# Relay_Sequencer.net
KiCad netlist of a schematic drawn in EAGLE
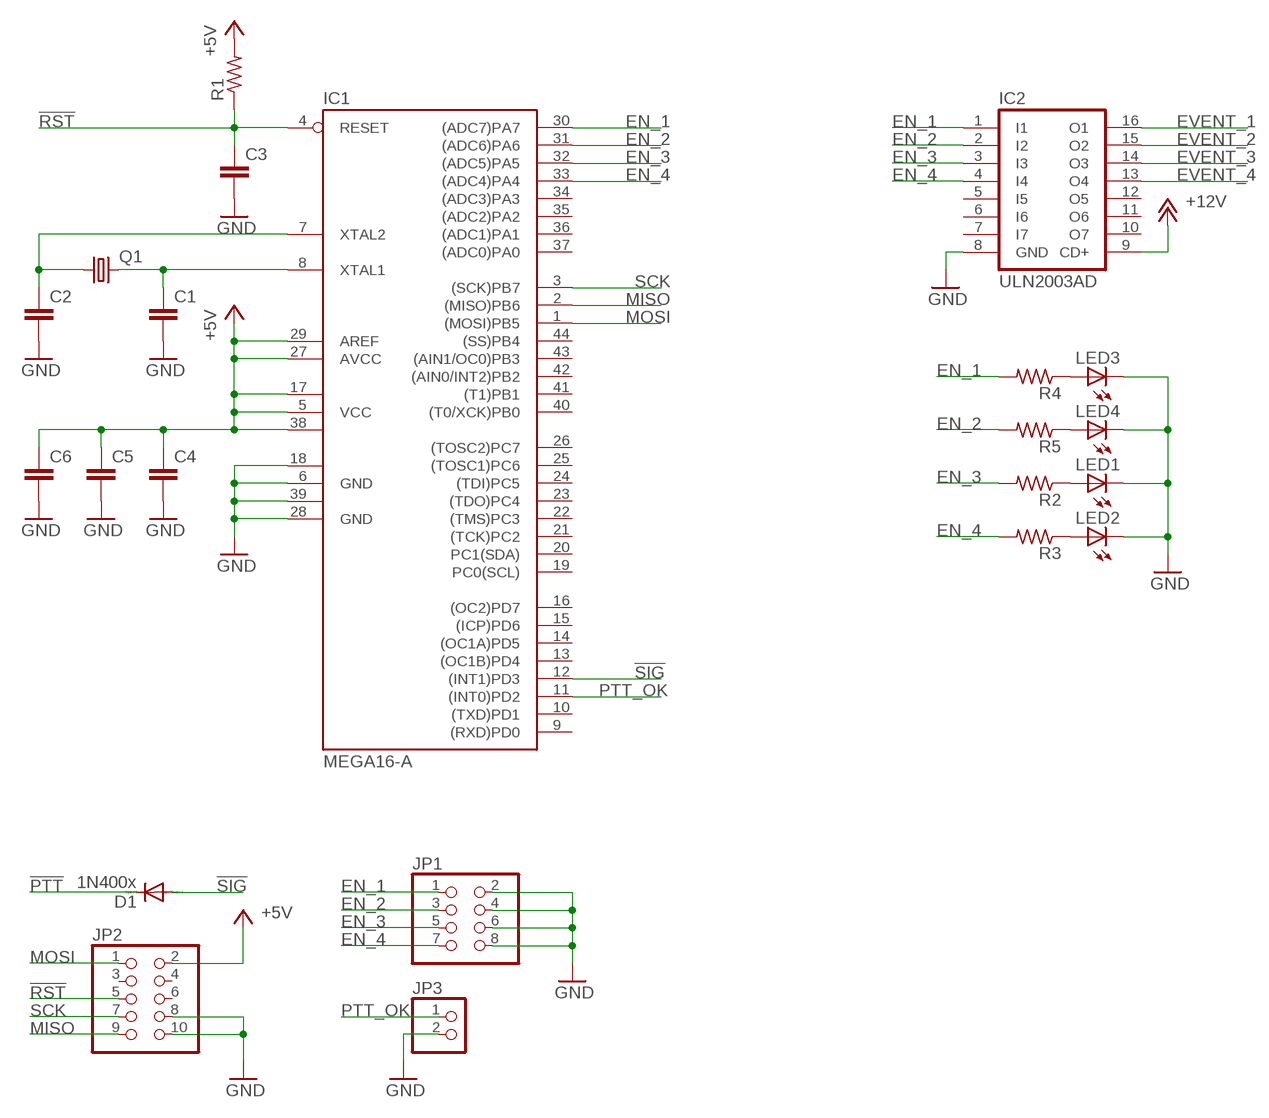
[diagram p0: schematic, sheet 1]

(export (version "E")
  (design (tool "Eeschema 10.0.6"))
  (components
    (comp (ref "C1")
      (value "C-EUC1206")
      (footprint "eagle-import:C1206")
      (libsource (lib "eagle-import") (part "C-EUC1206"))
    )
    (comp (ref "C2")
      (value "C-EUC1206")
      (footprint "eagle-import:C1206")
      (libsource (lib "eagle-import") (part "C-EUC1206"))
    )
    (comp (ref "C3")
      (value "C-EUC1206")
      (footprint "eagle-import:C1206")
      (libsource (lib "eagle-import") (part "C-EUC1206"))
    )
    (comp (ref "C4")
      (value "C-EUC1206")
      (footprint "eagle-import:C1206")
      (libsource (lib "eagle-import") (part "C-EUC1206"))
    )
    (comp (ref "C5")
      (value "C-EUC1206")
      (footprint "eagle-import:C1206")
      (libsource (lib "eagle-import") (part "C-EUC1206"))
    )
    (comp (ref "C6")
      (value "C-EUC1206")
      (footprint "eagle-import:C1206")
      (libsource (lib "eagle-import") (part "C-EUC1206"))
    )
    (comp (ref "D1")
      (value "1N400x")
      (footprint "eagle-import:DO35-10")
      (libsource (lib "eagle-import") (part "1N4148DO35-10"))
    )
    (comp (ref "IC1")
      (value "MEGA16-A")
      (footprint "eagle-import:TQFP44")
      (fields (field (name "MPN") "ATMEGA16-16AU"))
      (libsource (lib "eagle-import") (part "MEGA16-A"))
    )
    (comp (ref "IC2")
      (value "ULN2003AD")
      (footprint "eagle-import:SO16")
      (libsource (lib "eagle-import") (part "ULN2003AD"))
    )
    (comp (ref "JP1")
      (value "PINHD-2X4")
      (footprint "eagle-import:2X04")
      (libsource (lib "eagle-import") (part "PINHD-2X4"))
    )
    (comp (ref "JP2")
      (value "PINHD-2X5")
      (footprint "eagle-import:2X05")
      (libsource (lib "eagle-import") (part "PINHD-2X5"))
    )
    (comp (ref "JP3")
      (value "PINHD-1X2")
      (footprint "eagle-import:1X02")
      (libsource (lib "eagle-import") (part "PINHD-1X2"))
    )
    (comp (ref "LED1")
      (value "LED3MM")
      (footprint "eagle-import:LED3MM")
      (libsource (lib "eagle-import") (part "LED3MM"))
    )
    (comp (ref "LED2")
      (value "LED3MM")
      (footprint "eagle-import:LED3MM")
      (libsource (lib "eagle-import") (part "LED3MM"))
    )
    (comp (ref "LED3")
      (value "LED3MM")
      (footprint "eagle-import:LED3MM")
      (libsource (lib "eagle-import") (part "LED3MM"))
    )
    (comp (ref "LED4")
      (value "LED3MM")
      (footprint "eagle-import:LED3MM")
      (libsource (lib "eagle-import") (part "LED3MM"))
    )
    (comp (ref "Q1")
      (value "CRYSTALHC49S")
      (footprint "eagle-import:HC49_S")
      (libsource (lib "eagle-import") (part "CRYSTALHC49S"))
    )
    (comp (ref "R1")
      (value "R-US_M1206")
      (footprint "eagle-import:M1206")
      (libsource (lib "eagle-import") (part "R-US_M1206"))
    )
    (comp (ref "R2")
      (value "R-US_M1206")
      (footprint "eagle-import:M1206")
      (libsource (lib "eagle-import") (part "R-US_M1206"))
    )
    (comp (ref "R3")
      (value "R-US_M1206")
      (footprint "eagle-import:M1206")
      (libsource (lib "eagle-import") (part "R-US_M1206"))
    )
    (comp (ref "R4")
      (value "R-US_M1206")
      (footprint "eagle-import:M1206")
      (libsource (lib "eagle-import") (part "R-US_M1206"))
    )
    (comp (ref "R5")
      (value "R-US_M1206")
      (footprint "eagle-import:M1206")
      (libsource (lib "eagle-import") (part "R-US_M1206"))
    )
  )
  (nets
    (net (code "1") (name "+5V") (class "Default")
      (node (ref "C4") (pin "1") (pinfunction "1_1") (pintype "passive"))
      (node (ref "C5") (pin "1") (pinfunction "1_1") (pintype "passive"))
      (node (ref "C6") (pin "1") (pinfunction "1_1") (pintype "passive"))
      (node (ref "IC1") (pin "17") (pinfunction "VCC1_17") (pintype "power_in"))
      (node (ref "IC1") (pin "27") (pinfunction "AVCC_27") (pintype "power_in"))
      (node (ref "IC1") (pin "29") (pinfunction "AREF_29") (pintype "passive"))
      (node (ref "IC1") (pin "38") (pinfunction "VCC2_38") (pintype "power_in"))
      (node (ref "IC1") (pin "5") (pinfunction "VCC_5") (pintype "power_in"))
      (node (ref "JP2") (pin "2") (pinfunction "2_2") (pintype "passive"))
      (node (ref "R1") (pin "2") (pinfunction "2_2") (pintype "passive"))
    )
    (net (code "2") (name "+12V") (class "Default")
      (node (ref "IC2") (pin "9") (pinfunction "CD+_9") (pintype "passive"))
    )
    (net (code "3") (name "/EN_1") (class "Default")
      (node (ref "IC1") (pin "30") (pinfunction "(ADC7)PA7_30") (pintype "bidirectional"))
      (node (ref "IC2") (pin "1") (pinfunction "I1_1") (pintype "input"))
      (node (ref "JP1") (pin "1") (pinfunction "1_1") (pintype "passive"))
      (node (ref "R4") (pin "2") (pinfunction "2_2") (pintype "passive"))
    )
    (net (code "4") (name "/EN_2") (class "Default")
      (node (ref "IC1") (pin "31") (pinfunction "(ADC6)PA6_31") (pintype "bidirectional"))
      (node (ref "IC2") (pin "2") (pinfunction "I2_2") (pintype "input"))
      (node (ref "JP1") (pin "3") (pinfunction "3_3") (pintype "passive"))
      (node (ref "R5") (pin "2") (pinfunction "2_2") (pintype "passive"))
    )
    (net (code "5") (name "/EN_3") (class "Default")
      (node (ref "IC1") (pin "32") (pinfunction "(ADC5)PA5_32") (pintype "bidirectional"))
      (node (ref "IC2") (pin "3") (pinfunction "I3_3") (pintype "input"))
      (node (ref "JP1") (pin "5") (pinfunction "5_5") (pintype "passive"))
      (node (ref "R2") (pin "2") (pinfunction "2_2") (pintype "passive"))
    )
    (net (code "6") (name "/EN_4") (class "Default")
      (node (ref "IC1") (pin "33") (pinfunction "(ADC4)PA4_33") (pintype "bidirectional"))
      (node (ref "IC2") (pin "4") (pinfunction "I4_4") (pintype "input"))
      (node (ref "JP1") (pin "7") (pinfunction "7_7") (pintype "passive"))
      (node (ref "R3") (pin "2") (pinfunction "2_2") (pintype "passive"))
    )
    (net (code "7") (name "/EVENT_1") (class "Default")
      (node (ref "IC2") (pin "16") (pinfunction "O1_16") (pintype "open_collector"))
    )
    (net (code "8") (name "/EVENT_2") (class "Default")
      (node (ref "IC2") (pin "15") (pinfunction "O2_15") (pintype "open_collector"))
    )
    (net (code "9") (name "/EVENT_3") (class "Default")
      (node (ref "IC2") (pin "14") (pinfunction "O3_14") (pintype "open_collector"))
    )
    (net (code "10") (name "/EVENT_4") (class "Default")
      (node (ref "IC2") (pin "13") (pinfunction "O4_13") (pintype "open_collector"))
    )
    (net (code "11") (name "/MISO") (class "Default")
      (node (ref "IC1") (pin "2") (pinfunction "(MISO)PB6_2") (pintype "bidirectional"))
      (node (ref "JP2") (pin "9") (pinfunction "9_9") (pintype "passive"))
    )
    (net (code "12") (name "/MOSI") (class "Default")
      (node (ref "IC1") (pin "1") (pinfunction "(MOSI)PB5_1") (pintype "bidirectional"))
      (node (ref "JP2") (pin "1") (pinfunction "1_1") (pintype "passive"))
    )
    (net (code "13") (name "/PTT_OK") (class "Default")
      (node (ref "IC1") (pin "11") (pinfunction "(INT0)PD2_11") (pintype "bidirectional"))
      (node (ref "JP3") (pin "1") (pinfunction "1_1") (pintype "passive"))
    )
    (net (code "14") (name "/SCK") (class "Default")
      (node (ref "IC1") (pin "3") (pinfunction "(SCK)PB7_3") (pintype "bidirectional"))
      (node (ref "JP2") (pin "7") (pinfunction "7_7") (pintype "passive"))
    )
    (net (code "15") (name "/~{PTT}") (class "Default")
      (node (ref "D1") (pin "C") (pinfunction "C_C") (pintype "passive"))
    )
    (net (code "16") (name "/~{RST}") (class "Default")
      (node (ref "C3") (pin "1") (pinfunction "1_1") (pintype "passive"))
      (node (ref "IC1") (pin "4") (pinfunction "RESET_4") (pintype "input"))
      (node (ref "JP2") (pin "5") (pinfunction "5_5") (pintype "passive"))
      (node (ref "R1") (pin "1") (pinfunction "1_1") (pintype "passive"))
    )
    (net (code "17") (name "/~{SIG}") (class "Default")
      (node (ref "D1") (pin "A") (pinfunction "A_A") (pintype "passive"))
      (node (ref "IC1") (pin "12") (pinfunction "(INT1)PD3_12") (pintype "bidirectional"))
    )
    (net (code "18") (name "GND") (class "Default")
      (node (ref "C1") (pin "2") (pinfunction "2_2") (pintype "passive"))
      (node (ref "C2") (pin "2") (pinfunction "2_2") (pintype "passive"))
      (node (ref "C3") (pin "2") (pinfunction "2_2") (pintype "passive"))
      (node (ref "C4") (pin "2") (pinfunction "2_2") (pintype "passive"))
      (node (ref "C5") (pin "2") (pinfunction "2_2") (pintype "passive"))
      (node (ref "C6") (pin "2") (pinfunction "2_2") (pintype "passive"))
      (node (ref "IC1") (pin "18") (pinfunction "GND1_18") (pintype "power_in"))
      (node (ref "IC1") (pin "28") (pinfunction "GND_28") (pintype "power_in"))
      (node (ref "IC1") (pin "39") (pinfunction "GND2_39") (pintype "power_in"))
      (node (ref "IC1") (pin "6") (pinfunction "GND_6") (pintype "power_in"))
      (node (ref "IC2") (pin "8") (pinfunction "GND_8") (pintype "power_in"))
      (node (ref "JP1") (pin "2") (pinfunction "2_2") (pintype "passive"))
      (node (ref "JP1") (pin "4") (pinfunction "4_4") (pintype "passive"))
      (node (ref "JP1") (pin "6") (pinfunction "6_6") (pintype "passive"))
      (node (ref "JP1") (pin "8") (pinfunction "8_8") (pintype "passive"))
      (node (ref "JP2") (pin "10") (pinfunction "10_10") (pintype "passive"))
      (node (ref "JP2") (pin "8") (pinfunction "8_8") (pintype "passive"))
      (node (ref "JP3") (pin "2") (pinfunction "2_2") (pintype "passive"))
      (node (ref "LED1") (pin "K") (pinfunction "C_K") (pintype "passive"))
      (node (ref "LED2") (pin "K") (pinfunction "C_K") (pintype "passive"))
      (node (ref "LED3") (pin "K") (pinfunction "C_K") (pintype "passive"))
      (node (ref "LED4") (pin "K") (pinfunction "C_K") (pintype "passive"))
    )
    (net (code "19") (name "Net-(IC1-XTAL1)") (class "Default")
      (node (ref "C1") (pin "1") (pinfunction "1_1") (pintype "passive"))
      (node (ref "IC1") (pin "8") (pinfunction "XTAL1_8") (pintype "bidirectional"))
      (node (ref "Q1") (pin "2") (pinfunction "2_2") (pintype "passive"))
    )
    (net (code "20") (name "Net-(IC1-XTAL2)") (class "Default")
      (node (ref "C2") (pin "1") (pinfunction "1_1") (pintype "passive"))
      (node (ref "IC1") (pin "7") (pinfunction "XTAL2_7") (pintype "bidirectional"))
      (node (ref "Q1") (pin "1") (pinfunction "1_1") (pintype "passive"))
    )
    (net (code "21") (name "Net-(LED1-PadA)") (class "Default")
      (node (ref "LED1") (pin "A") (pinfunction "A_A") (pintype "passive"))
      (node (ref "R2") (pin "1") (pinfunction "1_1") (pintype "passive"))
    )
    (net (code "22") (name "Net-(LED2-PadA)") (class "Default")
      (node (ref "LED2") (pin "A") (pinfunction "A_A") (pintype "passive"))
      (node (ref "R3") (pin "1") (pinfunction "1_1") (pintype "passive"))
    )
    (net (code "23") (name "Net-(LED3-PadA)") (class "Default")
      (node (ref "LED3") (pin "A") (pinfunction "A_A") (pintype "passive"))
      (node (ref "R4") (pin "1") (pinfunction "1_1") (pintype "passive"))
    )
    (net (code "24") (name "Net-(LED4-PadA)") (class "Default")
      (node (ref "LED4") (pin "A") (pinfunction "A_A") (pintype "passive"))
      (node (ref "R5") (pin "1") (pinfunction "1_1") (pintype "passive"))
    )
    (net (code "25") (name "unconnected-(IC1-(ADC0)PA0-Pad37)") (class "Default")
      (node (ref "IC1") (pin "37") (pinfunction "(ADC0)PA0_37") (pintype "bidirectional"))
    )
    (net (code "26") (name "unconnected-(IC1-(ADC1)PA1-Pad36)") (class "Default")
      (node (ref "IC1") (pin "36") (pinfunction "(ADC1)PA1_36") (pintype "bidirectional"))
    )
    (net (code "27") (name "unconnected-(IC1-(ADC2)PA2-Pad35)") (class "Default")
      (node (ref "IC1") (pin "35") (pinfunction "(ADC2)PA2_35") (pintype "bidirectional"))
    )
    (net (code "28") (name "unconnected-(IC1-(ADC3)PA3-Pad34)") (class "Default")
      (node (ref "IC1") (pin "34") (pinfunction "(ADC3)PA3_34") (pintype "bidirectional"))
    )
    (net (code "29") (name "unconnected-(IC1-(AIN0{slash}INT2)PB2-Pad42)") (class "Default")
      (node (ref "IC1") (pin "42") (pinfunction "(AIN0/INT2)PB2_42") (pintype "bidirectional"))
    )
    (net (code "30") (name "unconnected-(IC1-(AIN1{slash}OC0)PB3-Pad43)") (class "Default")
      (node (ref "IC1") (pin "43") (pinfunction "(AIN1/OC0)PB3_43") (pintype "bidirectional"))
    )
    (net (code "31") (name "unconnected-(IC1-(ICP)PD6-Pad15)") (class "Default")
      (node (ref "IC1") (pin "15") (pinfunction "(ICP)PD6_15") (pintype "bidirectional"))
    )
    (net (code "32") (name "unconnected-(IC1-(OC1A)PD5-Pad14)") (class "Default")
      (node (ref "IC1") (pin "14") (pinfunction "(OC1A)PD5_14") (pintype "bidirectional"))
    )
    (net (code "33") (name "unconnected-(IC1-(OC1B)PD4-Pad13)") (class "Default")
      (node (ref "IC1") (pin "13") (pinfunction "(OC1B)PD4_13") (pintype "bidirectional"))
    )
    (net (code "34") (name "unconnected-(IC1-(OC2)PD7-Pad16)") (class "Default")
      (node (ref "IC1") (pin "16") (pinfunction "(OC2)PD7_16") (pintype "bidirectional"))
    )
    (net (code "35") (name "unconnected-(IC1-(RXD)PD0-Pad9)") (class "Default")
      (node (ref "IC1") (pin "9") (pinfunction "(RXD)PD0_9") (pintype "bidirectional"))
    )
    (net (code "36") (name "unconnected-(IC1-(SS)PB4-Pad44)") (class "Default")
      (node (ref "IC1") (pin "44") (pinfunction "(SS)PB4_44") (pintype "bidirectional"))
    )
    (net (code "37") (name "unconnected-(IC1-(T0{slash}XCK)PB0-Pad40)") (class "Default")
      (node (ref "IC1") (pin "40") (pinfunction "(T0/XCK)PB0_40") (pintype "bidirectional"))
    )
    (net (code "38") (name "unconnected-(IC1-(T1)PB1-Pad41)") (class "Default")
      (node (ref "IC1") (pin "41") (pinfunction "(T1)PB1_41") (pintype "bidirectional"))
    )
    (net (code "39") (name "unconnected-(IC1-(TCK)PC2-Pad21)") (class "Default")
      (node (ref "IC1") (pin "21") (pinfunction "(TCK)PC2_21") (pintype "bidirectional"))
    )
    (net (code "40") (name "unconnected-(IC1-(TDI)PC5-Pad24)") (class "Default")
      (node (ref "IC1") (pin "24") (pinfunction "(TDI)PC5_24") (pintype "bidirectional"))
    )
    (net (code "41") (name "unconnected-(IC1-(TDO)PC4-Pad23)") (class "Default")
      (node (ref "IC1") (pin "23") (pinfunction "(TDO)PC4_23") (pintype "bidirectional"))
    )
    (net (code "42") (name "unconnected-(IC1-(TMS)PC3-Pad22)") (class "Default")
      (node (ref "IC1") (pin "22") (pinfunction "(TMS)PC3_22") (pintype "bidirectional"))
    )
    (net (code "43") (name "unconnected-(IC1-(TOSC1)PC6-Pad25)") (class "Default")
      (node (ref "IC1") (pin "25") (pinfunction "(TOSC1)PC6_25") (pintype "bidirectional"))
    )
    (net (code "44") (name "unconnected-(IC1-(TOSC2)PC7-Pad26)") (class "Default")
      (node (ref "IC1") (pin "26") (pinfunction "(TOSC2)PC7_26") (pintype "bidirectional"))
    )
    (net (code "45") (name "unconnected-(IC1-(TXD)PD1-Pad10)") (class "Default")
      (node (ref "IC1") (pin "10") (pinfunction "(TXD)PD1_10") (pintype "bidirectional"))
    )
    (net (code "46") (name "unconnected-(IC1-PC0(SCL)-Pad19)") (class "Default")
      (node (ref "IC1") (pin "19") (pinfunction "PC0(SCL)_19") (pintype "bidirectional"))
    )
    (net (code "47") (name "unconnected-(IC1-PC1(SDA)-Pad20)") (class "Default")
      (node (ref "IC1") (pin "20") (pinfunction "PC1(SDA)_20") (pintype "bidirectional"))
    )
    (net (code "48") (name "unconnected-(IC2-I5-Pad5)") (class "Default")
      (node (ref "IC2") (pin "5") (pinfunction "I5_5") (pintype "input"))
    )
    (net (code "49") (name "unconnected-(IC2-I6-Pad6)") (class "Default")
      (node (ref "IC2") (pin "6") (pinfunction "I6_6") (pintype "input"))
    )
    (net (code "50") (name "unconnected-(IC2-I7-Pad7)") (class "Default")
      (node (ref "IC2") (pin "7") (pinfunction "I7_7") (pintype "input"))
    )
    (net (code "51") (name "unconnected-(IC2-O5-Pad12)") (class "Default")
      (node (ref "IC2") (pin "12") (pinfunction "O5_12") (pintype "open_collector"))
    )
    (net (code "52") (name "unconnected-(IC2-O6-Pad11)") (class "Default")
      (node (ref "IC2") (pin "11") (pinfunction "O6_11") (pintype "open_collector"))
    )
    (net (code "53") (name "unconnected-(IC2-O7-Pad10)") (class "Default")
      (node (ref "IC2") (pin "10") (pinfunction "O7_10") (pintype "open_collector"))
    )
    (net (code "54") (name "unconnected-(JP2-Pad3)") (class "Default")
      (node (ref "JP2") (pin "3") (pinfunction "3_3") (pintype "passive"))
    )
    (net (code "55") (name "unconnected-(JP2-Pad4)") (class "Default")
      (node (ref "JP2") (pin "4") (pinfunction "4_4") (pintype "passive"))
    )
    (net (code "56") (name "unconnected-(JP2-Pad6)") (class "Default")
      (node (ref "JP2") (pin "6") (pinfunction "6_6") (pintype "passive"))
    )
  )
)
